# Power_Distribution.net
KiCad netlist of a schematic drawn in Altium Designer
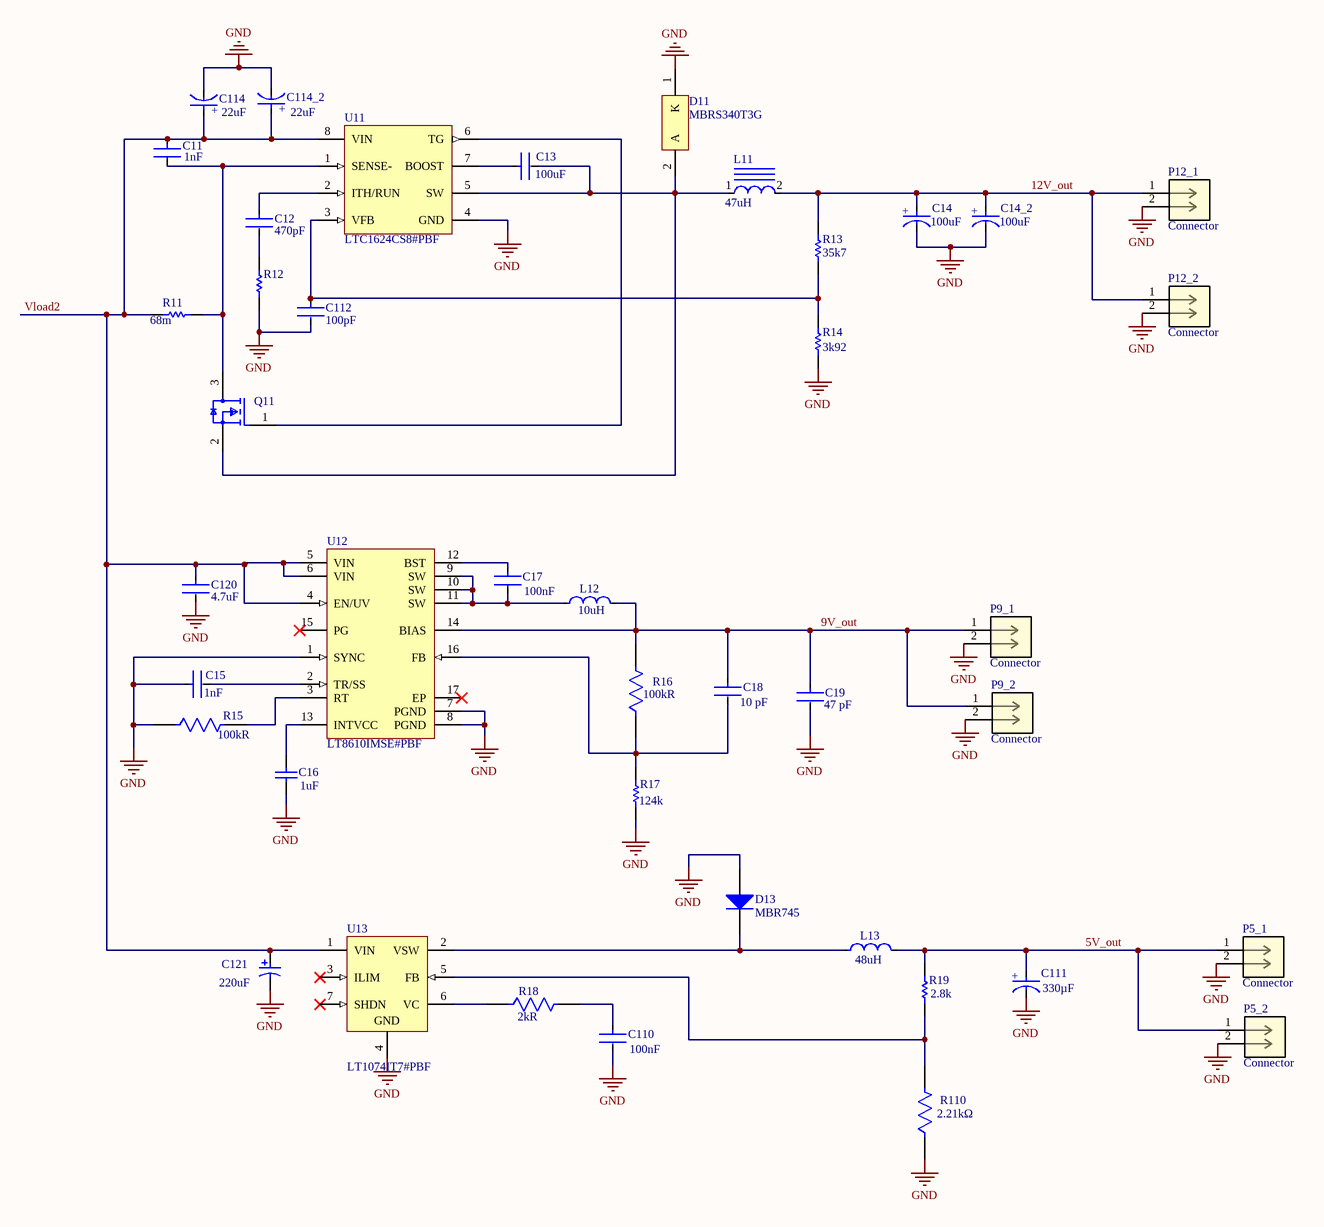
[diagram p0: Power Distribution.SchDoc]

(export (version "E")
  (design (tool "Eeschema 10.0.6"))
  (components
    (comp (ref "C11")
      (value "08055C102KAT2A")
      (footprint "FP-0805-L_2_01_0_2-W_1_25-IPC_B")
      (description "General Purpose Ceramic Capacitor, 0805, 1nF, 10%, X7R, 0.15, 50V")
      (fields
        (field (name "VOLTAGE") "50V")
        (field (name "TOLERANCE") "10%")
        (field (name "CAPACITANCE") "1nF")
      )
      (libsource (lib "Altium Content Vault") (part "02cd4be3c70576c341d710602a673aa"))
    )
    (comp (ref "C12")
      (value "08055C471KAT2A")
      (footprint "FP-0805-L_2_01_0_2-W_1_25-IPC_B")
      (description "General Purpose Ceramic Capacitor, 0805, 470pF, 10%, X7R, 0.15, 50V")
      (fields
        (field (name "CAPACITANCE") "470pF")
        (field (name "VOLTAGE") "50V")
        (field (name "TOLERANCE") "10%")
      )
      (libsource (lib "Altium Content Vault") (part "02cd4be3c70576c341d710602a673aa"))
    )
    (comp (ref "C13")
      (value "GRM21BR60J107ME15L")
      (footprint "FP-GRM21B-0_2-e0_2_0_7-IPC_B")
      (description "Chip Multilayer Ceramic Capacitors for General Purpose, 0805, 100uF, X5R, 15%, 20%, 6.3V")
      (fields (field (name "TOLERANCE") "20%") (field (name "CAPACITANCE") "100uF"))
      (libsource (lib "Altium Content Vault") (part "b4654b650e69147ec39a6b967a45e02"))
    )
    (comp (ref "C14")
      (value "EEUFR1H101")
      (footprint "FP-RAD-TH-D_8_0_5-L_11_5-MFG")
      (description "Aluminum Electrolytic Capacitors (Radial Lead Type) 100uF ±20% 50V")
      (fields
        (field (name "CAPACITANCE") "100uF")
        (field (name "VOLTAGE") "50V")
        (field (name "TOLERANCE") "20%")
      )
      (libsource (lib "Altium Content Vault") (part "a00bbbee19879c290e62620ae7e47b1"))
    )
    (comp (ref "C14_2")
      (value "EEUFR1H101")
      (footprint "FP-RAD-TH-D_8_0_5-L_11_5-MFG")
      (description "Aluminum Electrolytic Capacitors (Radial Lead Type) 100uF ±20% 50V")
      (fields
        (field (name "CAPACITANCE") "100uF")
        (field (name "VOLTAGE") "50V")
        (field (name "TOLERANCE") "20%")
      )
      (libsource (lib "Altium Content Vault") (part "a00bbbee19879c290e62620ae7e47b1"))
    )
    (comp (ref "C15")
      (value "08055C102KAT2A")
      (footprint "FP-0805-L_2_01_0_2-W_1_25-IPC_B")
      (description "General Purpose Ceramic Capacitor, 0805, 1nF, 10%, X7R, 0.15, 50V")
      (fields
        (field (name "VOLTAGE") "50V")
        (field (name "TOLERANCE") "10%")
        (field (name "CAPACITANCE") "1nF")
      )
      (libsource (lib "Altium Content Vault") (part "02cd4be3c70576c341d710602a673aa"))
    )
    (comp (ref "C16")
      (value "1uF")
      (footprint "CAPC2013X140X50NL20T25")
      (fields (field (name "MANUFACTURER") "Kemet") (field (name "PART NUMBER") "C0805C105K5RACTU"))
      (libsource (lib "Altium Content Vault") (part "CAP"))
    )
    (comp (ref "C17")
      (value "08051C104KAT2A")
      (footprint "FP-0805-L_2_01_0_2-W_1_25-IPC_B")
      (description "General Purpose Ceramic Capacitor, 0805, 100nF, 10%, X7R, 15%, 100V")
      (fields
        (field (name "CAPACITANCE") "100nF")
        (field (name "VOLTAGE") "100V")
        (field (name "TOLERANCE") "10%")
      )
      (libsource (lib "Altium Content Vault") (part "b4654b650e69147ec39a6b967a45e02"))
    )
    (comp (ref "C18")
      (value "10 pF")
      (footprint "FP-C0805C-DN-IPC_B")
      (description "Capacitor; Ceramic; Cap 10 pF; Tol 5%; Vol-Rtg 50 VDC; SMT; 0805; COG (NPO); Tape&Reel")
      (fields
        (field (name "OCTOPART") "https://octopart.com/c0805c100j5gactu-kemet-104357")
        (field (name "MANUFACTURER PART NUMBER") "C0805C100J5GACTU")
      )
      (libsource (lib "Altium Content Vault") (part "b4654b650e69147ec39a6b967a45e02"))
    )
    (comp (ref "C19")
      (value "47 pF")
      (footprint "FP-C0805C-DN-MFG")
      (description "CAP CER 47PF 100V 5% NP0 0805")
      (fields
        (field (name "MANUFACTURER") "KEMET")
        (field (name "OCTOPART") "https://octopart.com/c0805c470j1gactu-kemet-9138638")
      )
      (libsource (lib "Altium Content Vault") (part "b4654b650e69147ec39a6b967a45e02"))
    )
    (comp (ref "C110")
      (value "08051C104KAT2A")
      (footprint "FP-0805-L_2_01_0_2-W_1_25-IPC_B")
      (description "General Purpose Ceramic Capacitor, 0805, 100nF, 10%, X7R, 15%, 100V")
      (fields
        (field (name "CAPACITANCE") "100nF")
        (field (name "VOLTAGE") "100V")
        (field (name "TOLERANCE") "10%")
      )
      (libsource (lib "Altium Content Vault") (part "b4654b650e69147ec39a6b967a45e02"))
    )
    (comp (ref "C111")
      (value "EEEFK0J331XP")
      (footprint "FP-FKD8-MFG")
      (fields
        (field (name "TOLERANCE") "20%")
        (field (name "CAPACITANCE") "330µF")
        (field (name "VOLTAGE") "6.3V")
      )
      (libsource (lib "Altium Content Vault") (part "cf48714ba7e38822c1575c7ec0b6d1f"))
    )
    (comp (ref "C112")
      (value "08051A101JAT2A")
      (footprint "FP-0805-L_2_01_0_2-W_1_25-IPC_B")
      (description "General Purpose Ceramic Capacitor, 0805, 100pF, 5%, C0G, 30ppm/°C, 100V")
      (fields
        (field (name "TOLERANCE") "5%")
        (field (name "VOLTAGE") "100V")
        (field (name "CAPACITANCE") "100pF")
      )
      (libsource (lib "Altium Content Vault") (part "02cd4be3c70576c341d710602a673aa"))
    )
    (comp (ref "C114")
      (value "22uF")
      (footprint "FP-FKF-MFG")
      (description "CAP ALUM 22UF 20% 100V SMD")
      (fields (field (name "Comment") "EEE-FK2A220P"))
      (libsource (lib "Altium Content Vault") (part "a00bbbee19879c290e62620ae7e47b1"))
    )
    (comp (ref "C114_2")
      (value "22uF")
      (footprint "FP-FKF-MFG")
      (description "CAP ALUM 22UF 20% 100V SMD")
      (fields (field (name "Comment") "EEE-FK2A220P"))
      (libsource (lib "Altium Content Vault") (part "a00bbbee19879c290e62620ae7e47b1"))
    )
    (comp (ref "C120")
      (value "C0805C475K8PACTU")
      (footprint "FP-C0805C475K8PACTU-MFG")
      (description "CAP CER 4.7UF 10V X5R 0805")
      (fields
        (field (name "CAPACITANCE") "4.7uF")
        (field (name "TOLERANCE") "10%")
        (field (name "VOLTAGE") "10V")
      )
      (libsource (lib "Altium Content Vault") (part "e9c51b7dd13d4faca003ae77663ab08"))
    )
    (comp (ref "C121")
      (value "220uF")
      (footprint "PNSC-EEE-FK1E221P_N")
      (fields (field (name "MANUFACTURER") "Panasonic") (field (name "Comment") "EEE-FK1E221P"))
      (libsource (lib "Altium Content Vault") (part "CAP-P-2"))
    )
    (comp (ref "D11")
      (value "MBRS340T3G")
      (footprint "ONSC-SMC-2-403-03_V")
      (description "Schottky Power Rectifier, 2-Pin SMC, Pb-Free, Tape and Reel")
      (fields (field (name "MANUFACTURER") "On Semiconductor"))
      (libsource (lib "Altium Content Vault") (part "ONSC-D-K1A2-2_A"))
    )
    (comp (ref "D13")
      (value "MBR745")
      (footprint "ONSC-TO-220-2-221B-04_E")
      (description "SWITCHMODE(TM) Power Rectifier, 2-Pin TO-220, Tube")
      (fields (field (name "MANUFACTURER") "On Semiconductor"))
      (libsource (lib "Altium Content Vault") (part "ONSC-D-K1A3-2_A"))
    )
    (comp (ref "L11")
      (value "DR127-470-R")
      (footprint "FP-DR127-MFG")
      (description "FIXED IND 47UH 2.95A 71.9 MOHM")
      (fields (field (name "INDUCTANCE") "47uH") (field (name "TOLERANCE") "20%"))
      (libsource (lib "Altium Content Vault") (part "d07565f5f22d47b7aaed31362611f1d"))
    )
    (comp (ref "L12")
      (value "CBC3225T100MR")
      (footprint "FP-CB3225-IPC_B")
      (description "SMD Inductors 10uH ±20% 0.9A 0.1729Ω 1210")
      (fields (field (name "INDUCTANCE") "10uH") (field (name "TOLERANCE") "20%"))
      (libsource (lib "Altium Content Vault") (part "725321dda6339637d4d059423bc1c3c"))
    )
    (comp (ref "L13")
      (value "48uH")
      (footprint "FP-PCC-M0754M-MFG")
      (description "FIXED IND 47UH 2.9A 172 MOHM SMD")
      (fields
        (field (name "MANUFACTURER") "Panasonic")
        (field (name "MANUFACTURER PART NUMBER") "ETQ-P5M470YFM")
      )
      (libsource (lib "Altium Content Vault") (part "725321dda6339637d4d059423bc1c3c"))
    )
    (comp (ref "P5_1")
      (value "Connector")
      (footprint "CONN_B2B-XH-A_JST")
      (description "Header B2B-XH-A, 2.50mm, 2-contacts, top entry, THT /1000/box")
      (fields (field (name "MANUFACTURER") "JST") (field (name "MANUFACTURER PART NUMBER") "B2B-XH-A"))
      (libsource (lib "Schlib1") (part "B2B-XH-A"))
    )
    (comp (ref "P5_2")
      (value "Connector")
      (footprint "CONN_B2B-XH-A_JST")
      (description "Header B2B-XH-A, 2.50mm, 2-contacts, top entry, THT /1000/box")
      (fields (field (name "MANUFACTURER") "JST") (field (name "MANUFACTURER PART NUMBER") "B2B-XH-A"))
      (libsource (lib "Schlib1") (part "B2B-XH-A"))
    )
    (comp (ref "P9_1")
      (value "Connector")
      (footprint "CONN_B2B-XH-A_JST")
      (description "Header B2B-XH-A, 2.50mm, 2-contacts, top entry, THT /1000/box")
      (fields (field (name "MANUFACTURER") "JST") (field (name "MANUFACTURER PART NUMBER") "B2B-XH-A"))
      (libsource (lib "Schlib1") (part "B2B-XH-A"))
    )
    (comp (ref "P9_2")
      (value "Connector")
      (footprint "CONN_B2B-XH-A_JST")
      (description "Header B2B-XH-A, 2.50mm, 2-contacts, top entry, THT /1000/box")
      (fields (field (name "MANUFACTURER") "JST") (field (name "MANUFACTURER PART NUMBER") "B2B-XH-A"))
      (libsource (lib "Schlib1") (part "B2B-XH-A"))
    )
    (comp (ref "P12_1")
      (value "Connector")
      (footprint "CONN_B2B-XH-A_JST")
      (description "Header B2B-XH-A, 2.50mm, 2-contacts, top entry, THT /1000/box")
      (fields (field (name "MANUFACTURER") "JST") (field (name "MANUFACTURER PART NUMBER") "B2B-XH-A"))
      (libsource (lib "Schlib1") (part "B2B-XH-A"))
    )
    (comp (ref "P12_2")
      (value "Connector")
      (footprint "CONN_B2B-XH-A_JST")
      (description "Header B2B-XH-A, 2.50mm, 2-contacts, top entry, THT /1000/box")
      (fields (field (name "MANUFACTURER") "JST") (field (name "MANUFACTURER PART NUMBER") "B2B-XH-A"))
      (libsource (lib "Schlib1") (part "B2B-XH-A"))
    )
    (comp (ref "Q11")
      (value "DMN3404L-7")
      (footprint "FP-SOT23-MFG")
      (description "MOSFET N-CH 30V 5.8A SOT-23")
      (fields
        (field (name "OCTOPART") "https://octopart.com/dmn3404l-7-diodes+inc.-12409285")
        (field (name "MANUFACTURER") "Diodes Inc.")
      )
      (libsource (lib "Altium Content Vault") (part "0a9ea7c96deaaede766a5b531c28de0"))
    )
    (comp (ref "R11")
      (value "68m")
      (footprint "RESC1608X55X30NL15T15")
      (fields (field (name "MANUFACTURER") "Panasonic") (field (name "PART NUMBER") "ERJ3BWFR068V"))
      (libsource (lib "Altium Content Vault") (part "RES"))
    )
    (comp (ref "R12")
      (value "ERJ-6GEYJ682V")
      (footprint "RESC2013X70X40NL20T20")
      (fields (field (name "MANUFACTURER") "Panasonic"))
      (libsource (lib "Altium Content Vault") (part "RES"))
    )
    (comp (ref "R13")
      (value "35k7")
      (footprint "RESC2013X70X40NL20T20")
      (fields (field (name "MANUFACTURER") "Panasonic") (field (name "PART NUMBER") "ERJ-6ENF3572V"))
      (libsource (lib "Altium Content Vault") (part "RES"))
    )
    (comp (ref "R14")
      (value "3k92")
      (footprint "RESC2013X50X30NL20T20")
      (fields (field (name "MANUFACTURER") "Vishay Dale") (field (name "PART NUMBER") "CRCW08053K92FKEA"))
      (libsource (lib "Altium Content Vault") (part "RES"))
    )
    (comp (ref "R15")
      (value "ERA-6AEB104V")
      (footprint "FP-ERA6A-IPC_B")
      (description "RES 100K OHM 0.1% 1/8W 0805")
      (fields (field (name "TOLERANCE") "0.1%") (field (name "RESISTANCE") "100kR"))
      (libsource (lib "Altium Content Vault") (part "1029c3af85768c4190bb7ad29bc67b5"))
    )
    (comp (ref "R16")
      (value "RC0805FR-07100KL")
      (footprint "FP-RC0805-0_6-IPC_B")
      (description "RES 100K OHM 1% 1/8W 0805")
      (fields (field (name "TOLERANCE") "1%") (field (name "RESISTANCE") "100kR"))
      (libsource (lib "Altium Content Vault") (part "1029c3af85768c4190bb7ad29bc67b5"))
    )
    (comp (ref "R17")
      (value "124k")
      (footprint "RESC2013X70X40NL20T20")
      (fields (field (name "MANUFACTURER") "Panasonic") (field (name "PART NUMBER") "ERJ-6ENF1243V"))
      (libsource (lib "Altium Content Vault") (part "RES"))
    )
    (comp (ref "R18")
      (value "CRCW08052K00FKEA")
      (footprint "FP-CRCW0805-e3-IPC_B")
      (description "RES Thick Film, 2kΩ, 1%, 0.125W, 100ppm/°C, 0805")
      (fields (field (name "TOLERANCE") "1%") (field (name "RESISTANCE") "2kR"))
      (libsource (lib "Altium Content Vault") (part "1029c3af85768c4190bb7ad29bc67b5"))
    )
    (comp (ref "R19")
      (value "2.8k")
      (footprint "RESC2013X70X40NL20T20")
      (fields (field (name "MANUFACTURER") "Panasonic") (field (name "PART NUMBER") "ERJ-6ENF2801V"))
      (libsource (lib "Altium Content Vault") (part "RES"))
    )
    (comp (ref "R110")
      (value "ERJ-6ENF2211V")
      (footprint "FP-ERJ6EN-MFG")
      (fields (field (name "TOLERANCE") "1%") (field (name "RESISTANCE") "2.21kΩ"))
      (libsource (lib "Altium Content Vault") (part "1029c3af85768c4190bb7ad29bc67b5"))
    )
    (comp (ref "U11")
      (value "LTC1624CS8#PBF")
      (footprint "LT-S8-8_N")
      (description "High Efficiency N-Channel Switching Regulator Controller, 8-pin SOIC (S8-8), 0 to 70 degC, Pb-Free")
      (fields (field (name "MANUFACTURER") "Linear Technology"))
      (libsource (lib "Altium Content Vault") (part "LT-LTC1624-S8-8"))
    )
    (comp (ref "U12")
      (value "LT8610IMSE#PBF")
      (footprint "LT-MSE-16-EDP_N")
      (fields (field (name "MANUFACTURER") "Linear Technology"))
      (libsource (lib "Altium Content Vault") (part "LT-LT8610-MSE-16"))
    )
    (comp (ref "U13")
      (value "LT1074IT7#PBF")
      (footprint "LT-T7-7-S_V")
      (description "Step-Down Switching Regulator, 7-pin FM (T7-7), -40 to 85 degC, Pb-Free")
      (fields (field (name "MANUFACTURER") "Linear Technology"))
      (libsource (lib "Altium Content Vault") (part "LT-LT107X-T7-7"))
    )
  )
  (nets
    (net (code "1") (name "/5V_out") (class "Default")
      (node (ref "C111") (pin "2") (pinfunction "A_2") (pintype "passive"))
      (node (ref "L13") (pin "2") (pinfunction "2_2") (pintype "passive"))
      (node (ref "P5_1") (pin "1") (pinfunction "1_1") (pintype "passive"))
      (node (ref "P5_2") (pin "1") (pinfunction "1_1") (pintype "passive"))
      (node (ref "R19") (pin "2") (pinfunction "2_2") (pintype "passive"))
    )
    (net (code "2") (name "/9V_out") (class "Default")
      (node (ref "C18") (pin "1") (pinfunction "1_1") (pintype "passive"))
      (node (ref "C19") (pin "1") (pinfunction "1_1") (pintype "passive"))
      (node (ref "L12") (pin "2") (pinfunction "2_2") (pintype "passive"))
      (node (ref "P9_1") (pin "1") (pinfunction "1_1") (pintype "passive"))
      (node (ref "P9_2") (pin "1") (pinfunction "1_1") (pintype "passive"))
      (node (ref "R16") (pin "2") (pinfunction "2_2") (pintype "passive"))
      (node (ref "U12") (pin "14") (pinfunction "BIAS_14") (pintype "power_in"))
    )
    (net (code "3") (name "/12V_out") (class "Default")
      (node (ref "C14") (pin "2") (pinfunction "A_2") (pintype "passive"))
      (node (ref "C14_2") (pin "2") (pinfunction "A_2") (pintype "passive"))
      (node (ref "L11") (pin "2") (pinfunction "2_2") (pintype "passive"))
      (node (ref "P12_1") (pin "1") (pinfunction "1_1") (pintype "passive"))
      (node (ref "P12_2") (pin "1") (pinfunction "1_1") (pintype "passive"))
      (node (ref "R13") (pin "2") (pinfunction "2_2") (pintype "passive"))
    )
    (net (code "4") (name "/Vload2") (class "Default")
      (node (ref "C11") (pin "1") (pinfunction "1_1") (pintype "passive"))
      (node (ref "C114") (pin "2") (pinfunction "A_2") (pintype "passive"))
      (node (ref "C114_2") (pin "2") (pinfunction "A_2") (pintype "passive"))
      (node (ref "C120") (pin "1") (pinfunction "1_1") (pintype "passive"))
      (node (ref "C121") (pin "1") (pinfunction "1_1") (pintype "passive"))
      (node (ref "R11") (pin "1") (pinfunction "1_1") (pintype "passive"))
      (node (ref "U11") (pin "8") (pinfunction "VIN_8") (pintype "power_in"))
      (node (ref "U12") (pin "4") (pinfunction "EN/UV_4") (pintype "input"))
      (node (ref "U12") (pin "5") (pinfunction "VIN_5") (pintype "power_in"))
      (node (ref "U12") (pin "6") (pinfunction "VIN_6") (pintype "power_in"))
      (node (ref "U13") (pin "1") (pinfunction "VIN_1") (pintype "power_in"))
    )
    (net (code "5") (name "GND") (class "Default")
      (node (ref "C110") (pin "2") (pinfunction "2_2") (pintype "passive"))
      (node (ref "C111") (pin "1") (pinfunction "C_1") (pintype "passive"))
      (node (ref "C112") (pin "2") (pinfunction "2_2") (pintype "passive"))
      (node (ref "C114") (pin "1") (pinfunction "C_1") (pintype "passive"))
      (node (ref "C114_2") (pin "1") (pinfunction "C_1") (pintype "passive"))
      (node (ref "C120") (pin "2") (pinfunction "2_2") (pintype "passive"))
      (node (ref "C121") (pin "2") (pinfunction "2_2") (pintype "passive"))
      (node (ref "C14") (pin "1") (pinfunction "C_1") (pintype "passive"))
      (node (ref "C14_2") (pin "1") (pinfunction "C_1") (pintype "passive"))
      (node (ref "C15") (pin "1") (pinfunction "1_1") (pintype "passive"))
      (node (ref "C16") (pin "1") (pinfunction "1_1") (pintype "passive"))
      (node (ref "C19") (pin "2") (pinfunction "2_2") (pintype "passive"))
      (node (ref "D11") (pin "1") (pinfunction "K_1") (pintype "passive"))
      (node (ref "D13") (pin "3") (pinfunction "A_3") (pintype "passive"))
      (node (ref "P12_1") (pin "2") (pinfunction "2_2") (pintype "passive"))
      (node (ref "P12_2") (pin "2") (pinfunction "2_2") (pintype "passive"))
      (node (ref "P5_1") (pin "2") (pinfunction "2_2") (pintype "passive"))
      (node (ref "P5_2") (pin "2") (pinfunction "2_2") (pintype "passive"))
      (node (ref "P9_1") (pin "2") (pinfunction "2_2") (pintype "passive"))
      (node (ref "P9_2") (pin "2") (pinfunction "2_2") (pintype "passive"))
      (node (ref "R110") (pin "1") (pinfunction "1_1") (pintype "passive"))
      (node (ref "R12") (pin "1") (pinfunction "1_1") (pintype "passive"))
      (node (ref "R14") (pin "1") (pinfunction "1_1") (pintype "passive"))
      (node (ref "R15") (pin "1") (pinfunction "1_1") (pintype "passive"))
      (node (ref "R17") (pin "1") (pinfunction "1_1") (pintype "passive"))
      (node (ref "U11") (pin "4") (pinfunction "GND_4") (pintype "power_in"))
      (node (ref "U12") (pin "1") (pinfunction "SYNC_1") (pintype "input"))
      (node (ref "U12") (pin "7") (pinfunction "PGND_7") (pintype "power_in"))
      (node (ref "U12") (pin "8") (pinfunction "PGND_8") (pintype "power_in"))
      (node (ref "U13") (pin "4") (pinfunction "GND_4") (pintype "power_in"))
    )
    (net (code "6") (name "Net-(C12-Pad2)") (class "Default")
      (node (ref "C12") (pin "2") (pinfunction "2_2") (pintype "passive"))
      (node (ref "R12") (pin "2") (pinfunction "2_2") (pintype "passive"))
    )
    (net (code "7") (name "Net-(C17-Pad2)") (class "Default")
      (node (ref "C17") (pin "2") (pinfunction "2_2") (pintype "passive"))
      (node (ref "L12") (pin "1") (pinfunction "1_1") (pintype "passive"))
      (node (ref "U12") (pin "10") (pinfunction "SW_10") (pintype "power_in"))
      (node (ref "U12") (pin "11") (pinfunction "SW_11") (pintype "power_in"))
      (node (ref "U12") (pin "9") (pinfunction "SW_9") (pintype "power_in"))
    )
    (net (code "8") (name "Net-(C110-Pad1)") (class "Default")
      (node (ref "C110") (pin "1") (pinfunction "1_1") (pintype "passive"))
      (node (ref "R18") (pin "2") (pinfunction "2_2") (pintype "passive"))
    )
    (net (code "9") (name "Net-(D11-A)") (class "Default")
      (node (ref "C13") (pin "2") (pinfunction "2_2") (pintype "passive"))
      (node (ref "D11") (pin "2") (pinfunction "A_2") (pintype "passive"))
      (node (ref "L11") (pin "1") (pinfunction "1_1") (pintype "passive"))
      (node (ref "Q11") (pin "2") (pinfunction "S_2") (pintype "passive"))
      (node (ref "U11") (pin "5") (pinfunction "SW_5") (pintype "passive"))
    )
    (net (code "10") (name "Net-(D13-K)") (class "Default")
      (node (ref "D13") (pin "1") (pinfunction "K_1") (pintype "passive"))
      (node (ref "L13") (pin "1") (pinfunction "1_1") (pintype "passive"))
      (node (ref "U13") (pin "2") (pinfunction "VSW_2") (pintype "power_in"))
    )
    (net (code "11") (name "Net-(Q11-D)") (class "Default")
      (node (ref "C11") (pin "2") (pinfunction "2_2") (pintype "passive"))
      (node (ref "Q11") (pin "3") (pinfunction "D_3") (pintype "passive"))
      (node (ref "R11") (pin "2") (pinfunction "2_2") (pintype "passive"))
      (node (ref "U11") (pin "1") (pinfunction "SENSE-_1") (pintype "input"))
    )
    (net (code "12") (name "Net-(Q11-G)") (class "Default")
      (node (ref "Q11") (pin "1") (pinfunction "G_1") (pintype "passive"))
      (node (ref "U11") (pin "6") (pinfunction "TG_6") (pintype "output"))
    )
    (net (code "13") (name "Net-(U11-BOOST)") (class "Default")
      (node (ref "C13") (pin "1") (pinfunction "1_1") (pintype "passive"))
      (node (ref "U11") (pin "7") (pinfunction "BOOST_7") (pintype "passive"))
    )
    (net (code "14") (name "Net-(U11-ITH{slash}RUN)") (class "Default")
      (node (ref "C12") (pin "1") (pinfunction "1_1") (pintype "passive"))
      (node (ref "U11") (pin "2") (pinfunction "ITH/RUN_2") (pintype "input"))
    )
    (net (code "15") (name "Net-(U11-VFB)") (class "Default")
      (node (ref "C112") (pin "1") (pinfunction "1_1") (pintype "passive"))
      (node (ref "R13") (pin "1") (pinfunction "1_1") (pintype "passive"))
      (node (ref "R14") (pin "2") (pinfunction "2_2") (pintype "passive"))
      (node (ref "U11") (pin "3") (pinfunction "VFB_3") (pintype "input"))
    )
    (net (code "16") (name "Net-(U12-BST)") (class "Default")
      (node (ref "C17") (pin "1") (pinfunction "1_1") (pintype "passive"))
      (node (ref "U12") (pin "12") (pinfunction "BST_12") (pintype "passive"))
    )
    (net (code "17") (name "Net-(U12-FB)") (class "Default")
      (node (ref "C18") (pin "2") (pinfunction "2_2") (pintype "passive"))
      (node (ref "R16") (pin "1") (pinfunction "1_1") (pintype "passive"))
      (node (ref "R17") (pin "2") (pinfunction "2_2") (pintype "passive"))
      (node (ref "U12") (pin "16") (pinfunction "FB_16") (pintype "input"))
    )
    (net (code "18") (name "Net-(U12-INTVCC)") (class "Default")
      (node (ref "C16") (pin "2") (pinfunction "2_2") (pintype "passive"))
      (node (ref "U12") (pin "13") (pinfunction "INTVCC_13") (pintype "power_in"))
    )
    (net (code "19") (name "Net-(U12-RT)") (class "Default")
      (node (ref "R15") (pin "2") (pinfunction "2_2") (pintype "passive"))
      (node (ref "U12") (pin "3") (pinfunction "RT_3") (pintype "passive"))
    )
    (net (code "20") (name "Net-(U12-TR{slash}SS)") (class "Default")
      (node (ref "C15") (pin "2") (pinfunction "2_2") (pintype "passive"))
      (node (ref "U12") (pin "2") (pinfunction "TR/SS_2") (pintype "input"))
    )
    (net (code "21") (name "Net-(U13-FB)") (class "Default")
      (node (ref "R110") (pin "2") (pinfunction "2_2") (pintype "passive"))
      (node (ref "R19") (pin "1") (pinfunction "1_1") (pintype "passive"))
      (node (ref "U13") (pin "5") (pinfunction "FB_5") (pintype "input"))
    )
    (net (code "22") (name "Net-(U13-VC)") (class "Default")
      (node (ref "R18") (pin "1") (pinfunction "1_1") (pintype "passive"))
      (node (ref "U13") (pin "6") (pinfunction "VC_6") (pintype "passive"))
    )
    (net (code "23") (name "unconnected-(U12-EP-Pad17)") (class "Default")
      (node (ref "U12") (pin "17") (pinfunction "EP_17") (pintype "power_in+no_connect"))
    )
    (net (code "24") (name "unconnected-(U12-PG-Pad15)") (class "Default")
      (node (ref "U12") (pin "15") (pinfunction "PG_15") (pintype "tri_state+no_connect"))
    )
    (net (code "25") (name "unconnected-(U13-ILIM-Pad3)") (class "Default")
      (node (ref "U13") (pin "3") (pinfunction "ILIM_3") (pintype "input+no_connect"))
    )
    (net (code "26") (name "unconnected-(U13-SHDN-Pad7)") (class "Default")
      (node (ref "U13") (pin "7") (pinfunction "SHDN_7") (pintype "input+no_connect"))
    )
  )
)
